# Reader.net
KiCad netlist of a schematic drawn in Altium Designer
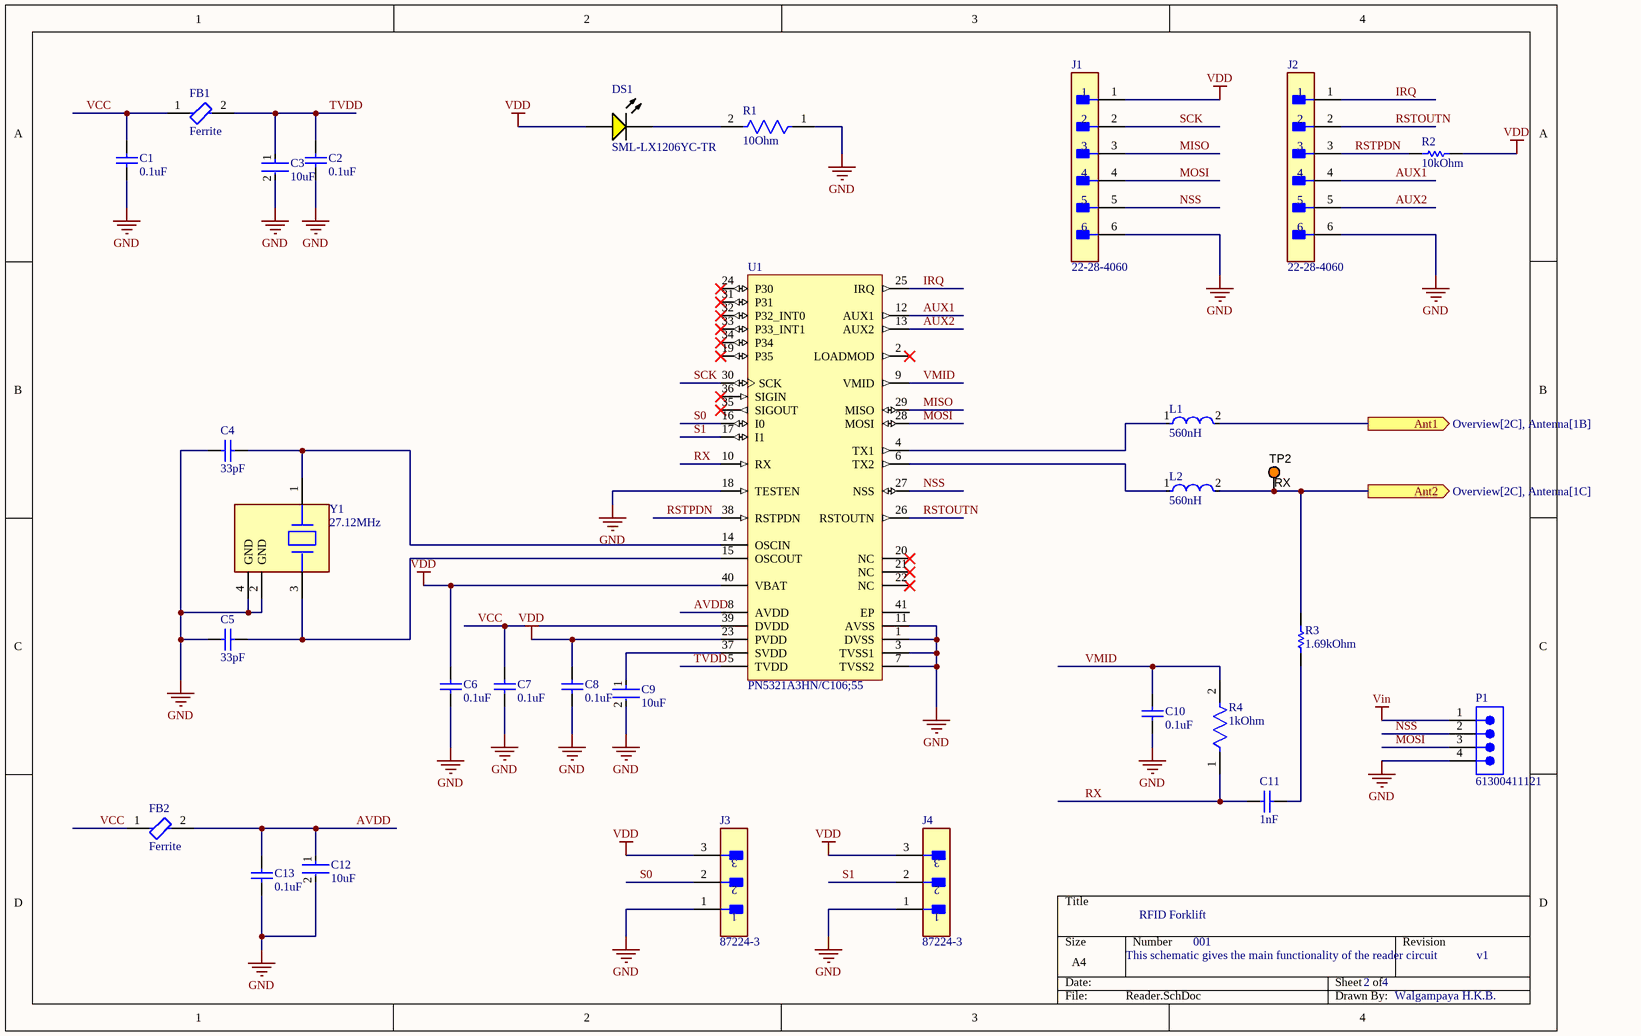
[diagram p0: Reader.SchDoc]

(export (version "E")
  (design (tool "Eeschema 10.0.6"))
  (components
    (comp (ref "C1")
      (value "0.1uF")
      (footprint "CAPC2013X140X50LL20T25")
      (description "08055C221KAT2A\r\n0805")
      (fields
        (field (name "PART NUMBER") "08055C221KAT2A")
        (field (name "MANUFACTURER") "AVX Interconnect / Elco")
      )
      (libsource (lib "Altium Content Vault") (part "CAP"))
    )
    (comp (ref "C2")
      (value "0.1uF")
      (footprint "CAPC2013X140X50LL20T25")
      (description "08055C221KAT2A\r\n0805")
      (fields
        (field (name "PART NUMBER") "08055C221KAT2A")
        (field (name "MANUFACTURER") "AVX Interconnect / Elco")
      )
      (libsource (lib "Altium Content Vault") (part "CAP"))
    )
    (comp (ref "C3")
      (value "10uF")
      (footprint "FP-CC1206-0_3-1_45-IPC_C")
      (description "CAP CER 1000PF 2KV X7R 1206")
      (fields (field (name "TOLERANCE") "10%") (field (name "VOLTAGE") "2kV"))
      (libsource (lib "Altium Content Vault") (part "02cd4be3c70576c341d710602a673aa"))
    )
    (comp (ref "C4")
      (value "33pF")
      (footprint "CAPC1608X90X35NL10T15")
      (description "0603")
      (fields (field (name "PART NUMBER") "GRM1885C1H330GA01D") (field (name "MANUFACTURER") "Murata"))
      (libsource (lib "Altium Content Vault") (part "CAP"))
    )
    (comp (ref "C5")
      (value "33pF")
      (footprint "CAPC1608X90X35NL10T15")
      (description "0603")
      (fields (field (name "PART NUMBER") "GRM1885C1H330GA01D") (field (name "MANUFACTURER") "Murata"))
      (libsource (lib "Altium Content Vault") (part "CAP"))
    )
    (comp (ref "C6")
      (value "0.1uF")
      (footprint "CAPC2013X140X50LL20T25")
      (description "08055C221KAT2A\r\n0805")
      (fields
        (field (name "PART NUMBER") "08055C221KAT2A")
        (field (name "MANUFACTURER") "AVX Interconnect / Elco")
      )
      (libsource (lib "Altium Content Vault") (part "CAP"))
    )
    (comp (ref "C7")
      (value "0.1uF")
      (footprint "CAPC2013X140X50LL20T25")
      (description "08055C221KAT2A\r\n0805")
      (fields
        (field (name "PART NUMBER") "08055C221KAT2A")
        (field (name "MANUFACTURER") "AVX Interconnect / Elco")
      )
      (libsource (lib "Altium Content Vault") (part "CAP"))
    )
    (comp (ref "C8")
      (value "0.1uF")
      (footprint "CAPC2013X140X50LL20T25")
      (description "08055C221KAT2A\r\n0805")
      (fields
        (field (name "PART NUMBER") "08055C221KAT2A")
        (field (name "MANUFACTURER") "AVX Interconnect / Elco")
      )
      (libsource (lib "Altium Content Vault") (part "CAP"))
    )
    (comp (ref "C9")
      (value "10uF")
      (footprint "FP-CC1206-0_3-1_45-IPC_C")
      (description "CAP CER 1000PF 2KV X7R 1206")
      (fields (field (name "TOLERANCE") "10%") (field (name "VOLTAGE") "2kV"))
      (libsource (lib "Altium Content Vault") (part "02cd4be3c70576c341d710602a673aa"))
    )
    (comp (ref "C10")
      (value "0.1uF")
      (footprint "CAPC2013X140X50LL20T25")
      (description "08055C221KAT2A\r\n0805")
      (fields
        (field (name "PART NUMBER") "08055C221KAT2A")
        (field (name "MANUFACTURER") "AVX Interconnect / Elco")
      )
      (libsource (lib "Altium Content Vault") (part "CAP"))
    )
    (comp (ref "C11")
      (value "1nF")
      (footprint "CAPC2013X140X50LL20T25")
      (description "08055C221KAT2A\r\n0805")
      (fields
        (field (name "PART NUMBER") "08055C221KAT2A")
        (field (name "MANUFACTURER") "AVX Interconnect / Elco")
      )
      (libsource (lib "Altium Content Vault") (part "CAP"))
    )
    (comp (ref "C12")
      (value "10uF")
      (footprint "FP-CC1206-0_3-1_45-IPC_C")
      (description "CAP CER 1000PF 2KV X7R 1206")
      (fields (field (name "TOLERANCE") "10%") (field (name "VOLTAGE") "2kV"))
      (libsource (lib "Altium Content Vault") (part "02cd4be3c70576c341d710602a673aa"))
    )
    (comp (ref "C13")
      (value "0.1uF")
      (footprint "CAPC2013X140X50LL20T25")
      (description "08055C221KAT2A\r\n0805")
      (fields
        (field (name "PART NUMBER") "08055C221KAT2A")
        (field (name "MANUFACTURER") "AVX Interconnect / Elco")
      )
      (libsource (lib "Altium Content Vault") (part "CAP"))
    )
    (comp (ref "DS1")
      (value "SML-LX1206YC-TR")
      (footprint "LUMX-SML-LX1206YC-TR_V")
      (description "Yellow LED, Water Clear Len, 585 nm, 2.1 V, -40 to 85 degC, 2-Pin SMD, RoHS, Tape and Reel")
      (fields (field (name "MANUFACTURER") "Lumex"))
      (libsource (lib "Altium Content Vault") (part "LED-YELLOW-AK-2"))
    )
    (comp (ref "FB1")
      (value "Ferrite")
      (footprint "FP-BLM21-0_2-t0_85-e0_5-MFG")
      (description "Chip Ferrite Bead, 0805, 470Ω @ 100MHz, 0.18Ω, 25%, 700mA\r\nBLM21AG471SN1D")
      (fields (field (name "TOLERANCE") "25%"))
      (libsource (lib "Altium Content Vault") (part "5f30dd21d616792df468990f7003faa"))
    )
    (comp (ref "FB2")
      (value "Ferrite")
      (footprint "FP-BLM21-0_2-t0_85-e0_5-MFG")
      (description "Chip Ferrite Bead, 0805, 470Ω @ 100MHz, 0.18Ω, 25%, 700mA\r\nBLM21AG471SN1D")
      (fields (field (name "TOLERANCE") "25%"))
      (libsource (lib "Altium Content Vault") (part "5f30dd21d616792df468990f7003faa"))
    )
    (comp (ref "J1")
      (value "22-28-4060")
      (footprint "FP-22-28-4060-MFG")
      (description "CONN HEADER VERT 6POS 2.54MM")
      (libsource (lib "Altium Content Vault") (part "f2cb566baf1c37ab5a3b8e90bbeafd6"))
    )
    (comp (ref "J2")
      (value "22-28-4060")
      (footprint "FP-22-28-4060-MFG")
      (description "CONN HEADER VERT 6POS 2.54MM")
      (libsource (lib "Altium Content Vault") (part "f2cb566baf1c37ab5a3b8e90bbeafd6"))
    )
    (comp (ref "J3")
      (value "87224-3")
      (footprint "FP-87224-3-MFG")
      (description "CONN HEADER VERT 3POS 2.54MM")
      (libsource (lib "Altium Content Vault") (part "0d3f023dd272f625e17a2be33dea85f"))
    )
    (comp (ref "J4")
      (value "87224-3")
      (footprint "FP-87224-3-MFG")
      (description "CONN HEADER VERT 3POS 2.54MM")
      (libsource (lib "Altium Content Vault") (part "0d3f023dd272f625e17a2be33dea85f"))
    )
    (comp (ref "L1")
      (value "560nH")
      (footprint "FP-LQM18FN_00-IPC_C")
      (description "FIXED IND 10UH 50MA 900 MOHM SMD")
      (fields (field (name "TOLERANCE") "20%"))
      (libsource (lib "Altium Content Vault") (part "725321dda6339637d4d059423bc1c3c"))
    )
    (comp (ref "L2")
      (value "560nH")
      (footprint "FP-LQM18FN_00-IPC_C")
      (description "FIXED IND 10UH 50MA 900 MOHM SMD")
      (fields (field (name "TOLERANCE") "20%"))
      (libsource (lib "Altium Content Vault") (part "725321dda6339637d4d059423bc1c3c"))
    )
    (comp (ref "P1")
      (value "61300411121")
      (footprint "61300411121")
      (libsource (lib "Altium Content Vault") (part "Header_Male_1R_04P"))
    )
    (comp (ref "R1")
      (value "10Ohm")
      (footprint "FP-RC0603-0_55-IPC_C")
      (description "RES 10K OHM 1% 1/10W 0603")
      (fields (field (name "TOLERANCE") "1%"))
      (libsource (lib "Altium Content Vault") (part "1029c3af85768c4190bb7ad29bc67b5"))
    )
    (comp (ref "R2")
      (value "10kOhm")
      (footprint "RESC2013X60X35NL10T20")
      (description "Chip Resistor, 10 KOhm, +/- 1%, 0.125 W, -55 to 155 degC, 0805 (2012 Metric), RoHS, Tape and Reel")
      (fields (field (name "MANUFACTURER") "Yageo"))
      (libsource (lib "Altium Content Vault") (part "RES-2"))
    )
    (comp (ref "R3")
      (value "1.69kOhm")
      (footprint "RESC3116X65X40ML10T20")
      (description "Chip Resistor, 10 Ohm, +/- 1%, 0.25 W, -55 to 155 degC, 1206 (3216 Metric), RoHS, Tape and Reel")
      (fields (field (name "MANUFACTURER") "Yageo") (field (name "TOLERANCE") "1%"))
      (libsource (lib "Altium Content Vault") (part "RES-2"))
    )
    (comp (ref "R4")
      (value "1kOhm")
      (footprint "FP-RC0603-0_55-IPC_C")
      (description "RES 10K OHM 1% 1/10W 0603")
      (fields (field (name "TOLERANCE") "1%"))
      (libsource (lib "Altium Content Vault") (part "1029c3af85768c4190bb7ad29bc67b5"))
    )
    (comp (ref "TP2")
      (value "RX")
      (footprint "KSTN-5003")
      (description "Test Point, Orange, 1-Pin THD, RoHS")
      (libsource (lib "Altium Content Vault") (part "TESTPOINT_ORANGE"))
    )
    (comp (ref "U1")
      (value "PN5321A3HN/C106;55")
      (footprint "NXP-HVQFN-40_L")
      (description "NFC Controller, 13.56 MHz, -30 to 85 degC, 40-Pin HVQFN (SOT618-1), RoHS, Tray")
      (fields (field (name "MANUFACTURER") "NXP Semiconductors"))
      (libsource (lib "Altium Content Vault") (part "NXP-PN5321A3HN-HVQFN-40"))
    )
    (comp (ref "Y1")
      (value "27.12MHz")
      (footprint "FP-ABM8-MFG")
      (description "Crystal 27.12MHz ±30ppm 18pF SMD-4 3.2mm x 2.5mm\r\nABM8-27.120MHZ-B4-T")
      (libsource (lib "Altium Content Vault") (part "dfdb7f9a12507849fb681da9a70121c"))
    )
  )
  (nets
    (net (code "1") (name "/AUX1") (class "Default")
      (node (ref "J2") (pin "4") (pinfunction "4_4") (pintype "passive"))
      (node (ref "U1") (pin "12") (pinfunction "AUX1_12") (pintype "output"))
    )
    (net (code "2") (name "/AUX2") (class "Default")
      (node (ref "J2") (pin "5") (pinfunction "5_5") (pintype "passive"))
      (node (ref "U1") (pin "13") (pinfunction "AUX2_13") (pintype "output"))
    )
    (net (code "3") (name "/AVDD") (class "Default")
      (node (ref "C12") (pin "1") (pinfunction "1_1") (pintype "passive"))
      (node (ref "C13") (pin "2") (pinfunction "2_2") (pintype "passive"))
      (node (ref "FB2") (pin "2") (pinfunction "2_2") (pintype "passive"))
      (node (ref "U1") (pin "8") (pinfunction "AVDD_8") (pintype "power_in"))
    )
    (net (code "4") (name "/Ant1") (class "Default")
      (node (ref "L1") (pin "2") (pinfunction "2_2") (pintype "passive"))
    )
    (net (code "5") (name "/Ant2") (class "Default")
      (node (ref "L2") (pin "2") (pinfunction "2_2") (pintype "passive"))
      (node (ref "R3") (pin "2") (pinfunction "2_2") (pintype "passive"))
      (node (ref "TP2") (pin "1") (pinfunction "1_1") (pintype "passive"))
    )
    (net (code "6") (name "/IRQ") (class "Default")
      (node (ref "J2") (pin "1") (pinfunction "1_1") (pintype "passive"))
      (node (ref "U1") (pin "25") (pinfunction "IRQ_25") (pintype "output"))
    )
    (net (code "7") (name "/MISO") (class "Default")
      (node (ref "J1") (pin "3") (pinfunction "3_3") (pintype "passive"))
      (node (ref "U1") (pin "29") (pinfunction "MISO_29") (pintype "bidirectional"))
    )
    (net (code "8") (name "/MOSI") (class "Default")
      (node (ref "J1") (pin "4") (pinfunction "4_4") (pintype "passive"))
      (node (ref "P1") (pin "3") (pinfunction "3_3") (pintype "passive"))
      (node (ref "U1") (pin "28") (pinfunction "MOSI_28") (pintype "bidirectional"))
    )
    (net (code "9") (name "/NSS") (class "Default")
      (node (ref "J1") (pin "5") (pinfunction "5_5") (pintype "passive"))
      (node (ref "P1") (pin "2") (pinfunction "2_2") (pintype "passive"))
      (node (ref "U1") (pin "27") (pinfunction "NSS_27") (pintype "bidirectional"))
    )
    (net (code "10") (name "/RSTOUTN") (class "Default")
      (node (ref "J2") (pin "2") (pinfunction "2_2") (pintype "passive"))
      (node (ref "U1") (pin "26") (pinfunction "RSTOUTN_26") (pintype "output"))
    )
    (net (code "11") (name "/RSTPDN") (class "Default")
      (node (ref "J2") (pin "3") (pinfunction "3_3") (pintype "passive"))
      (node (ref "R2") (pin "1") (pinfunction "1_1") (pintype "passive"))
      (node (ref "U1") (pin "38") (pinfunction "RSTPDN_38") (pintype "input"))
    )
    (net (code "12") (name "/RX") (class "Default")
      (node (ref "C11") (pin "2") (pinfunction "2_2") (pintype "passive"))
      (node (ref "R4") (pin "1") (pinfunction "1_1") (pintype "passive"))
      (node (ref "U1") (pin "10") (pinfunction "RX_10") (pintype "input"))
    )
    (net (code "13") (name "/S0") (class "Default")
      (node (ref "J3") (pin "2") (pinfunction "2_2") (pintype "passive"))
      (node (ref "U1") (pin "16") (pinfunction "I0_16") (pintype "bidirectional"))
    )
    (net (code "14") (name "/S1") (class "Default")
      (node (ref "J4") (pin "2") (pinfunction "2_2") (pintype "passive"))
      (node (ref "U1") (pin "17") (pinfunction "I1_17") (pintype "bidirectional"))
    )
    (net (code "15") (name "/SCK") (class "Default")
      (node (ref "J1") (pin "2") (pinfunction "2_2") (pintype "passive"))
      (node (ref "U1") (pin "30") (pinfunction "SCK_30") (pintype "bidirectional"))
    )
    (net (code "16") (name "/TVDD") (class "Default")
      (node (ref "C2") (pin "2") (pinfunction "2_2") (pintype "passive"))
      (node (ref "C3") (pin "1") (pinfunction "1_1") (pintype "passive"))
      (node (ref "FB1") (pin "2") (pinfunction "2_2") (pintype "passive"))
      (node (ref "U1") (pin "5") (pinfunction "TVDD_5") (pintype "power_in"))
    )
    (net (code "17") (name "/VCC") (class "Default")
      (node (ref "C1") (pin "2") (pinfunction "2_2") (pintype "passive"))
      (node (ref "C7") (pin "2") (pinfunction "2_2") (pintype "passive"))
      (node (ref "FB1") (pin "1") (pinfunction "1_1") (pintype "passive"))
      (node (ref "FB2") (pin "1") (pinfunction "1_1") (pintype "passive"))
      (node (ref "U1") (pin "39") (pinfunction "DVDD_39") (pintype "power_in"))
    )
    (net (code "18") (name "/VMID") (class "Default")
      (node (ref "C10") (pin "2") (pinfunction "2_2") (pintype "passive"))
      (node (ref "R4") (pin "2") (pinfunction "2_2") (pintype "passive"))
      (node (ref "U1") (pin "9") (pinfunction "VMID_9") (pintype "output"))
    )
    (net (code "19") (name "GND") (class "Default")
      (node (ref "C1") (pin "1") (pinfunction "1_1") (pintype "passive"))
      (node (ref "C10") (pin "1") (pinfunction "1_1") (pintype "passive"))
      (node (ref "C12") (pin "2") (pinfunction "2_2") (pintype "passive"))
      (node (ref "C13") (pin "1") (pinfunction "1_1") (pintype "passive"))
      (node (ref "C2") (pin "1") (pinfunction "1_1") (pintype "passive"))
      (node (ref "C3") (pin "2") (pinfunction "2_2") (pintype "passive"))
      (node (ref "C4") (pin "1") (pinfunction "1_1") (pintype "passive"))
      (node (ref "C5") (pin "1") (pinfunction "1_1") (pintype "passive"))
      (node (ref "C6") (pin "1") (pinfunction "1_1") (pintype "passive"))
      (node (ref "C7") (pin "1") (pinfunction "1_1") (pintype "passive"))
      (node (ref "C8") (pin "1") (pinfunction "1_1") (pintype "passive"))
      (node (ref "C9") (pin "2") (pinfunction "2_2") (pintype "passive"))
      (node (ref "J1") (pin "6") (pinfunction "6_6") (pintype "passive"))
      (node (ref "J2") (pin "6") (pinfunction "6_6") (pintype "passive"))
      (node (ref "J3") (pin "1") (pinfunction "1_1") (pintype "passive"))
      (node (ref "J4") (pin "1") (pinfunction "1_1") (pintype "passive"))
      (node (ref "P1") (pin "4") (pinfunction "4_4") (pintype "passive"))
      (node (ref "R1") (pin "1") (pinfunction "1_1") (pintype "passive"))
      (node (ref "U1") (pin "1") (pinfunction "DVSS_1") (pintype "power_in"))
      (node (ref "U1") (pin "11") (pinfunction "AVSS_11") (pintype "power_in"))
      (node (ref "U1") (pin "18") (pinfunction "TESTEN_18") (pintype "input"))
      (node (ref "U1") (pin "3") (pinfunction "TVSS1_3") (pintype "power_in"))
      (node (ref "U1") (pin "7") (pinfunction "TVSS2_7") (pintype "power_in"))
      (node (ref "Y1") (pin "2") (pinfunction "GND_2") (pintype "power_in"))
      (node (ref "Y1") (pin "4") (pinfunction "GND_4") (pintype "power_in"))
    )
    (net (code "20") (name "Net-(C11-Pad1)") (class "Default")
      (node (ref "C11") (pin "1") (pinfunction "1_1") (pintype "passive"))
      (node (ref "R3") (pin "1") (pinfunction "1_1") (pintype "passive"))
    )
    (net (code "21") (name "Net-(DS1-K)") (class "Default")
      (node (ref "DS1") (pin "2") (pinfunction "K_2") (pintype "passive"))
      (node (ref "R1") (pin "2") (pinfunction "2_2") (pintype "passive"))
    )
    (net (code "22") (name "Net-(U1-OSCIN)") (class "Default")
      (node (ref "C4") (pin "2") (pinfunction "2_2") (pintype "passive"))
      (node (ref "U1") (pin "14") (pinfunction "OSCIN_14") (pintype "passive"))
      (node (ref "Y1") (pin "1") (pinfunction "1_1") (pintype "passive"))
    )
    (net (code "23") (name "Net-(U1-OSCOUT)") (class "Default")
      (node (ref "C5") (pin "2") (pinfunction "2_2") (pintype "passive"))
      (node (ref "U1") (pin "15") (pinfunction "OSCOUT_15") (pintype "passive"))
      (node (ref "Y1") (pin "3") (pinfunction "3_3") (pintype "passive"))
    )
    (net (code "24") (name "Net-(U1-SVDD)") (class "Default")
      (node (ref "C9") (pin "1") (pinfunction "1_1") (pintype "passive"))
      (node (ref "U1") (pin "37") (pinfunction "SVDD_37") (pintype "power_in"))
    )
    (net (code "25") (name "Net-(U1-TX1)") (class "Default")
      (node (ref "L1") (pin "1") (pinfunction "1_1") (pintype "passive"))
      (node (ref "U1") (pin "4") (pinfunction "TX1_4") (pintype "output"))
    )
    (net (code "26") (name "Net-(U1-TX2)") (class "Default")
      (node (ref "L2") (pin "1") (pinfunction "1_1") (pintype "passive"))
      (node (ref "U1") (pin "6") (pinfunction "TX2_6") (pintype "output"))
    )
    (net (code "27") (name "VDD") (class "Default")
      (node (ref "C6") (pin "2") (pinfunction "2_2") (pintype "passive"))
      (node (ref "C8") (pin "2") (pinfunction "2_2") (pintype "passive"))
      (node (ref "DS1") (pin "1") (pinfunction "A_1") (pintype "passive"))
      (node (ref "J1") (pin "1") (pinfunction "1_1") (pintype "passive"))
      (node (ref "J3") (pin "3") (pinfunction "3_3") (pintype "passive"))
      (node (ref "J4") (pin "3") (pinfunction "3_3") (pintype "passive"))
      (node (ref "R2") (pin "2") (pinfunction "2_2") (pintype "passive"))
      (node (ref "U1") (pin "23") (pinfunction "PVDD_23") (pintype "power_in"))
      (node (ref "U1") (pin "40") (pinfunction "VBAT_40") (pintype "power_in"))
    )
    (net (code "28") (name "Vin") (class "Default")
      (node (ref "P1") (pin "1") (pinfunction "1_1") (pintype "passive"))
    )
    (net (code "29") (name "unconnected-(U1-EP-Pad41)") (class "Default")
      (node (ref "U1") (pin "41") (pinfunction "EP_41") (pintype "passive"))
    )
    (net (code "30") (name "unconnected-(U1-LOADMOD-Pad2)") (class "Default")
      (node (ref "U1") (pin "2") (pinfunction "LOADMOD_2") (pintype "output+no_connect"))
    )
    (net (code "31") (name "unconnected-(U1-NC-Pad20)") (class "Default")
      (node (ref "U1") (pin "20") (pinfunction "NC_20") (pintype "passive+no_connect"))
    )
    (net (code "32") (name "unconnected-(U1-NC-Pad21)") (class "Default")
      (node (ref "U1") (pin "21") (pinfunction "NC_21") (pintype "passive+no_connect"))
    )
    (net (code "33") (name "unconnected-(U1-NC-Pad22)") (class "Default")
      (node (ref "U1") (pin "22") (pinfunction "NC_22") (pintype "passive+no_connect"))
    )
    (net (code "34") (name "unconnected-(U1-P30-Pad24)") (class "Default")
      (node (ref "U1") (pin "24") (pinfunction "P30_24") (pintype "bidirectional+no_connect"))
    )
    (net (code "35") (name "unconnected-(U1-P31-Pad31)") (class "Default")
      (node (ref "U1") (pin "31") (pinfunction "P31_31") (pintype "bidirectional+no_connect"))
    )
    (net (code "36") (name "unconnected-(U1-P32_INT0-Pad32)") (class "Default")
      (node (ref "U1") (pin "32") (pinfunction "P32_INT0_32") (pintype "bidirectional+no_connect"))
    )
    (net (code "37") (name "unconnected-(U1-P33_INT1-Pad33)") (class "Default")
      (node (ref "U1") (pin "33") (pinfunction "P33_INT1_33") (pintype "bidirectional+no_connect"))
    )
    (net (code "38") (name "unconnected-(U1-P34-Pad34)") (class "Default")
      (node (ref "U1") (pin "34") (pinfunction "P34_34") (pintype "bidirectional+no_connect"))
    )
    (net (code "39") (name "unconnected-(U1-P35-Pad19)") (class "Default")
      (node (ref "U1") (pin "19") (pinfunction "P35_19") (pintype "bidirectional+no_connect"))
    )
    (net (code "40") (name "unconnected-(U1-SIGIN-Pad36)") (class "Default")
      (node (ref "U1") (pin "36") (pinfunction "SIGIN_36") (pintype "input+no_connect"))
    )
    (net (code "41") (name "unconnected-(U1-SIGOUT-Pad35)") (class "Default")
      (node (ref "U1") (pin "35") (pinfunction "SIGOUT_35") (pintype "output+no_connect"))
    )
  )
)
